# ECE411-Group6-V1.net
KiCad netlist of a schematic drawn in EAGLE
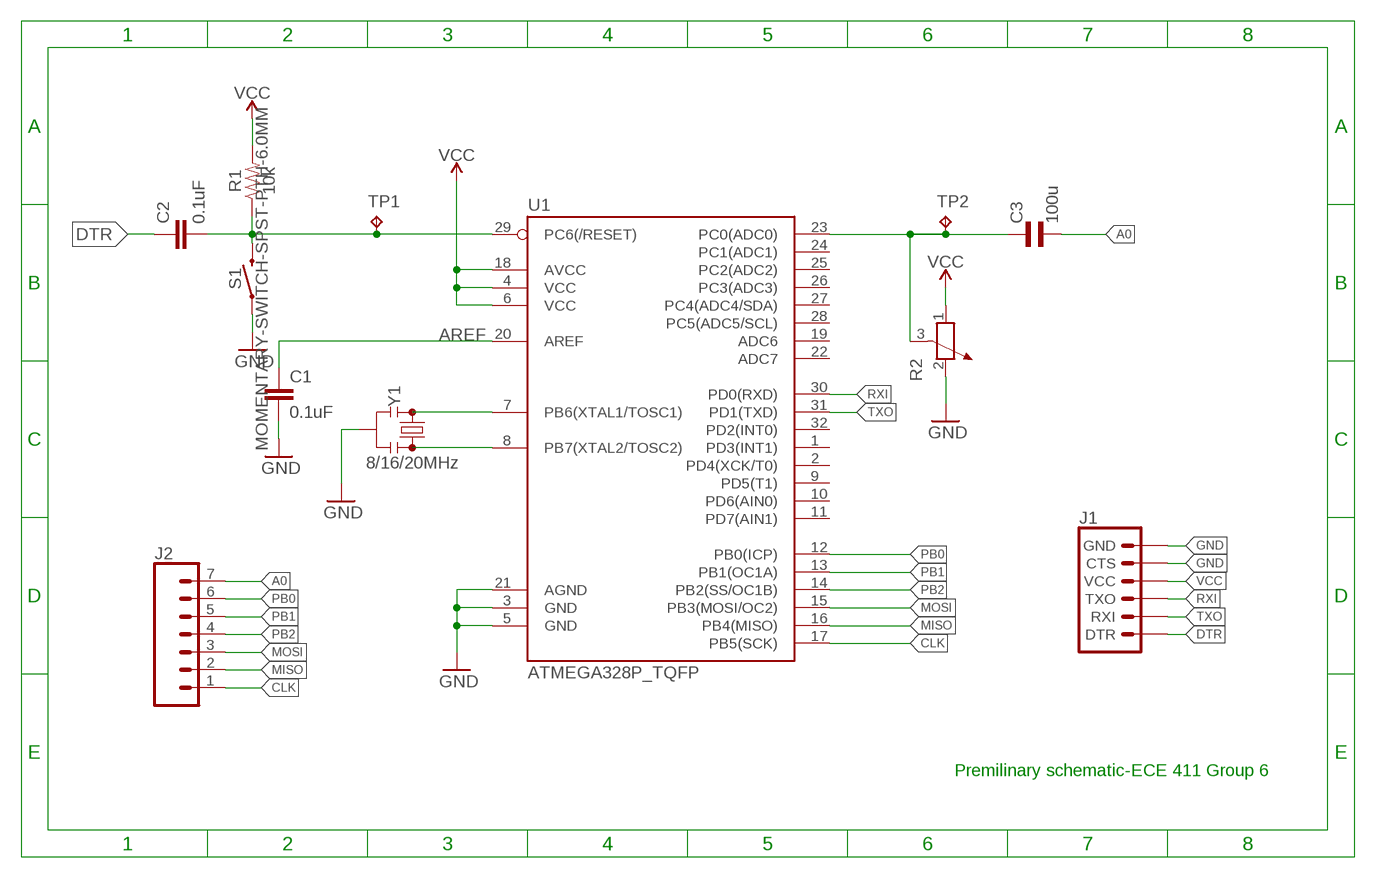
[diagram p0: schematic, sheet 1]

(export (version "E")
  (design (tool "Eeschema 10.0.6"))
  (components
    (comp (ref "C1")
      (value "0.1uF")
      (footprint "eagle-import:0603")
      (libsource (lib "eagle-import") (part "0.1UF-0603-25V-5%"))
    )
    (comp (ref "C2")
      (value "0.1uF")
      (footprint "eagle-import:0603")
      (libsource (lib "eagle-import") (part "0.1UF-0603-25V-5%"))
    )
    (comp (ref "C3")
      (value "100u")
      (footprint "eagle-import:EU25-10")
      (libsource (lib "eagle-import") (part "EL-BI25-10AXIAL"))
    )
    (comp (ref "J1")
      (value "6_PIN_SERIAL_TARGET")
      (footprint "eagle-import:1X06")
      (libsource (lib "eagle-import") (part "6_PIN_SERIAL_TARGET"))
    )
    (comp (ref "J2")
      (value "CONN_07")
      (footprint "eagle-import:1X07")
      (libsource (lib "eagle-import") (part "CONN_07"))
    )
    (comp (ref "R1")
      (value "10k")
      (footprint "eagle-import:0603")
      (libsource (lib "eagle-import") (part "10KOHM-0603-1/10W-1%"))
    )
    (comp (ref "R2")
      (value "POTENTIOMETER_PT-10")
      (footprint "eagle-import:PT-10")
      (libsource (lib "eagle-import") (part "POTENTIOMETER_PT-10"))
    )
    (comp (ref "S1")
      (value "MOMENTARY-SWITCH-SPST-PTH-6.0MM")
      (footprint "eagle-import:TACTILE_SWITCH_PTH_6.0MM")
      (libsource (lib "eagle-import") (part "MOMENTARY-SWITCH-SPST-PTH-6.0MM"))
    )
    (comp (ref "TP1")
      (value "TPB1,27")
      (footprint "eagle-import:B1,27")
      (libsource (lib "eagle-import") (part "TPB1,27"))
    )
    (comp (ref "TP2")
      (value "TPB1,27")
      (footprint "eagle-import:B1,27")
      (libsource (lib "eagle-import") (part "TPB1,27"))
    )
    (comp (ref "U1")
      (value "ATMEGA328P_TQFP")
      (footprint "eagle-import:TQFP32-08")
      (libsource (lib "eagle-import") (part "ATMEGA328P_TQFP"))
    )
    (comp (ref "Y1")
      (value "8/16/20MHz")
      (footprint "eagle-import:RESONATOR-SMD-3.2X1.3")
      (libsource (lib "eagle-import") (part "RESONATORSMD-3.2X1.3"))
    )
  )
  (nets
    (net (code "1") (name "/AREF") (class "Default")
      (node (ref "C1") (pin "1") (pinfunction "1_1") (pintype "passive"))
      (node (ref "U1") (pin "20") (pinfunction "AREF_20") (pintype "bidirectional"))
    )
    (net (code "2") (name "A0") (class "Default")
      (node (ref "C3") (pin "2") (pinfunction "2_2") (pintype "passive"))
      (node (ref "J2") (pin "7") (pinfunction "7_7") (pintype "passive"))
    )
    (net (code "3") (name "CLK") (class "Default")
      (node (ref "J2") (pin "1") (pinfunction "1_1") (pintype "passive"))
      (node (ref "U1") (pin "17") (pinfunction "PB5(SCK)_17") (pintype "bidirectional"))
    )
    (net (code "4") (name "DTR") (class "Default")
      (node (ref "C2") (pin "1") (pinfunction "1_1") (pintype "passive"))
      (node (ref "J1") (pin "1") (pinfunction "DTR_1") (pintype "passive"))
    )
    (net (code "5") (name "GND") (class "Default")
      (node (ref "C1") (pin "2") (pinfunction "2_2") (pintype "passive"))
      (node (ref "J1") (pin "5") (pinfunction "CTS_5") (pintype "passive"))
      (node (ref "J1") (pin "6") (pinfunction "GND_6") (pintype "passive"))
      (node (ref "R2") (pin "2") (pinfunction "2_2") (pintype "passive"))
      (node (ref "S1") (pin "1") (pinfunction "1_1") (pintype "passive"))
      (node (ref "U1") (pin "21") (pinfunction "AGND_21") (pintype "bidirectional"))
      (node (ref "U1") (pin "3") (pinfunction "GND_3") (pintype "bidirectional"))
      (node (ref "U1") (pin "5") (pinfunction "GND_5") (pintype "bidirectional"))
      (node (ref "Y1") (pin "2") (pinfunction "2_2") (pintype "passive"))
    )
    (net (code "6") (name "MISO") (class "Default")
      (node (ref "J2") (pin "2") (pinfunction "2_2") (pintype "passive"))
      (node (ref "U1") (pin "16") (pinfunction "PB4(MISO)_16") (pintype "bidirectional"))
    )
    (net (code "7") (name "MOSI") (class "Default")
      (node (ref "J2") (pin "3") (pinfunction "3_3") (pintype "passive"))
      (node (ref "U1") (pin "15") (pinfunction "PB3(MOSI/OC2)_15") (pintype "bidirectional"))
    )
    (net (code "8") (name "Net-(S1-2)") (class "Default")
      (node (ref "C2") (pin "2") (pinfunction "2_2") (pintype "passive"))
      (node (ref "R1") (pin "1") (pinfunction "1_1") (pintype "passive"))
      (node (ref "S1") (pin "3") (pinfunction "2_3") (pintype "passive"))
      (node (ref "TP1") (pin "TP") (pinfunction "TP_TP") (pintype "input"))
      (node (ref "U1") (pin "29") (pinfunction "PC6(/RESET)_29") (pintype "bidirectional"))
    )
    (net (code "9") (name "Net-(U1-PB6(XTAL1{slash}TOSC1))") (class "Default")
      (node (ref "U1") (pin "7") (pinfunction "PB6(XTAL1/TOSC1)_7") (pintype "bidirectional"))
      (node (ref "Y1") (pin "1") (pinfunction "1_1") (pintype "passive"))
    )
    (net (code "10") (name "Net-(U1-PB7(XTAL2{slash}TOSC2))") (class "Default")
      (node (ref "U1") (pin "8") (pinfunction "PB7(XTAL2/TOSC2)_8") (pintype "bidirectional"))
      (node (ref "Y1") (pin "3") (pinfunction "3_3") (pintype "passive"))
    )
    (net (code "11") (name "Net-(U1-PC0(ADC0))") (class "Default")
      (node (ref "C3") (pin "1") (pinfunction "1_1") (pintype "passive"))
      (node (ref "R2") (pin "3") (pinfunction "3_3") (pintype "passive"))
      (node (ref "TP2") (pin "TP") (pinfunction "TP_TP") (pintype "input"))
      (node (ref "U1") (pin "23") (pinfunction "PC0(ADC0)_23") (pintype "bidirectional"))
    )
    (net (code "12") (name "PB0") (class "Default")
      (node (ref "J2") (pin "6") (pinfunction "6_6") (pintype "passive"))
      (node (ref "U1") (pin "12") (pinfunction "PB0(ICP)_12") (pintype "bidirectional"))
    )
    (net (code "13") (name "PB1") (class "Default")
      (node (ref "J2") (pin "5") (pinfunction "5_5") (pintype "passive"))
      (node (ref "U1") (pin "13") (pinfunction "PB1(OC1A)_13") (pintype "bidirectional"))
    )
    (net (code "14") (name "PB2") (class "Default")
      (node (ref "J2") (pin "4") (pinfunction "4_4") (pintype "passive"))
      (node (ref "U1") (pin "14") (pinfunction "PB2(SS/OC1B)_14") (pintype "bidirectional"))
    )
    (net (code "15") (name "RXI") (class "Default")
      (node (ref "J1") (pin "3") (pinfunction "TXO_3") (pintype "passive"))
      (node (ref "U1") (pin "30") (pinfunction "PD0(RXD)_30") (pintype "bidirectional"))
    )
    (net (code "16") (name "TXO") (class "Default")
      (node (ref "J1") (pin "2") (pinfunction "RXI_2") (pintype "passive"))
      (node (ref "U1") (pin "31") (pinfunction "PD1(TXD)_31") (pintype "bidirectional"))
    )
    (net (code "17") (name "VCC") (class "Default")
      (node (ref "J1") (pin "4") (pinfunction "VCC_4") (pintype "passive"))
      (node (ref "R1") (pin "2") (pinfunction "2_2") (pintype "passive"))
      (node (ref "R2") (pin "1") (pinfunction "1_1") (pintype "passive"))
      (node (ref "U1") (pin "18") (pinfunction "AVCC_18") (pintype "bidirectional"))
      (node (ref "U1") (pin "4") (pinfunction "VCC_4") (pintype "bidirectional"))
      (node (ref "U1") (pin "6") (pinfunction "VCC_6") (pintype "bidirectional"))
    )
    (net (code "18") (name "unconnected-(U1-ADC6-Pad19)") (class "Default")
      (node (ref "U1") (pin "19") (pinfunction "ADC6_19") (pintype "bidirectional"))
    )
    (net (code "19") (name "unconnected-(U1-ADC7-Pad22)") (class "Default")
      (node (ref "U1") (pin "22") (pinfunction "ADC7_22") (pintype "bidirectional"))
    )
    (net (code "20") (name "unconnected-(U1-PC1(ADC1)-Pad24)") (class "Default")
      (node (ref "U1") (pin "24") (pinfunction "PC1(ADC1)_24") (pintype "bidirectional"))
    )
    (net (code "21") (name "unconnected-(U1-PC2(ADC2)-Pad25)") (class "Default")
      (node (ref "U1") (pin "25") (pinfunction "PC2(ADC2)_25") (pintype "bidirectional"))
    )
    (net (code "22") (name "unconnected-(U1-PC3(ADC3)-Pad26)") (class "Default")
      (node (ref "U1") (pin "26") (pinfunction "PC3(ADC3)_26") (pintype "bidirectional"))
    )
    (net (code "23") (name "unconnected-(U1-PC4(ADC4{slash}SDA)-Pad27)") (class "Default")
      (node (ref "U1") (pin "27") (pinfunction "PC4(ADC4/SDA)_27") (pintype "bidirectional"))
    )
    (net (code "24") (name "unconnected-(U1-PC5(ADC5{slash}SCL)-Pad28)") (class "Default")
      (node (ref "U1") (pin "28") (pinfunction "PC5(ADC5/SCL)_28") (pintype "bidirectional"))
    )
    (net (code "25") (name "unconnected-(U1-PD2(INT0)-Pad32)") (class "Default")
      (node (ref "U1") (pin "32") (pinfunction "PD2(INT0)_32") (pintype "bidirectional"))
    )
    (net (code "26") (name "unconnected-(U1-PD3(INT1)-Pad1)") (class "Default")
      (node (ref "U1") (pin "1") (pinfunction "PD3(INT1)_1") (pintype "bidirectional"))
    )
    (net (code "27") (name "unconnected-(U1-PD4(XCK{slash}T0)-Pad2)") (class "Default")
      (node (ref "U1") (pin "2") (pinfunction "PD4(XCK/T0)_2") (pintype "bidirectional"))
    )
    (net (code "28") (name "unconnected-(U1-PD5(T1)-Pad9)") (class "Default")
      (node (ref "U1") (pin "9") (pinfunction "PD5(T1)_9") (pintype "bidirectional"))
    )
    (net (code "29") (name "unconnected-(U1-PD6(AIN0)-Pad10)") (class "Default")
      (node (ref "U1") (pin "10") (pinfunction "PD6(AIN0)_10") (pintype "bidirectional"))
    )
    (net (code "30") (name "unconnected-(U1-PD7(AIN1)-Pad11)") (class "Default")
      (node (ref "U1") (pin "11") (pinfunction "PD7(AIN1)_11") (pintype "bidirectional"))
    )
  )
)
